# CPU_Board.net
KiCad netlist of a schematic drawn in EAGLE
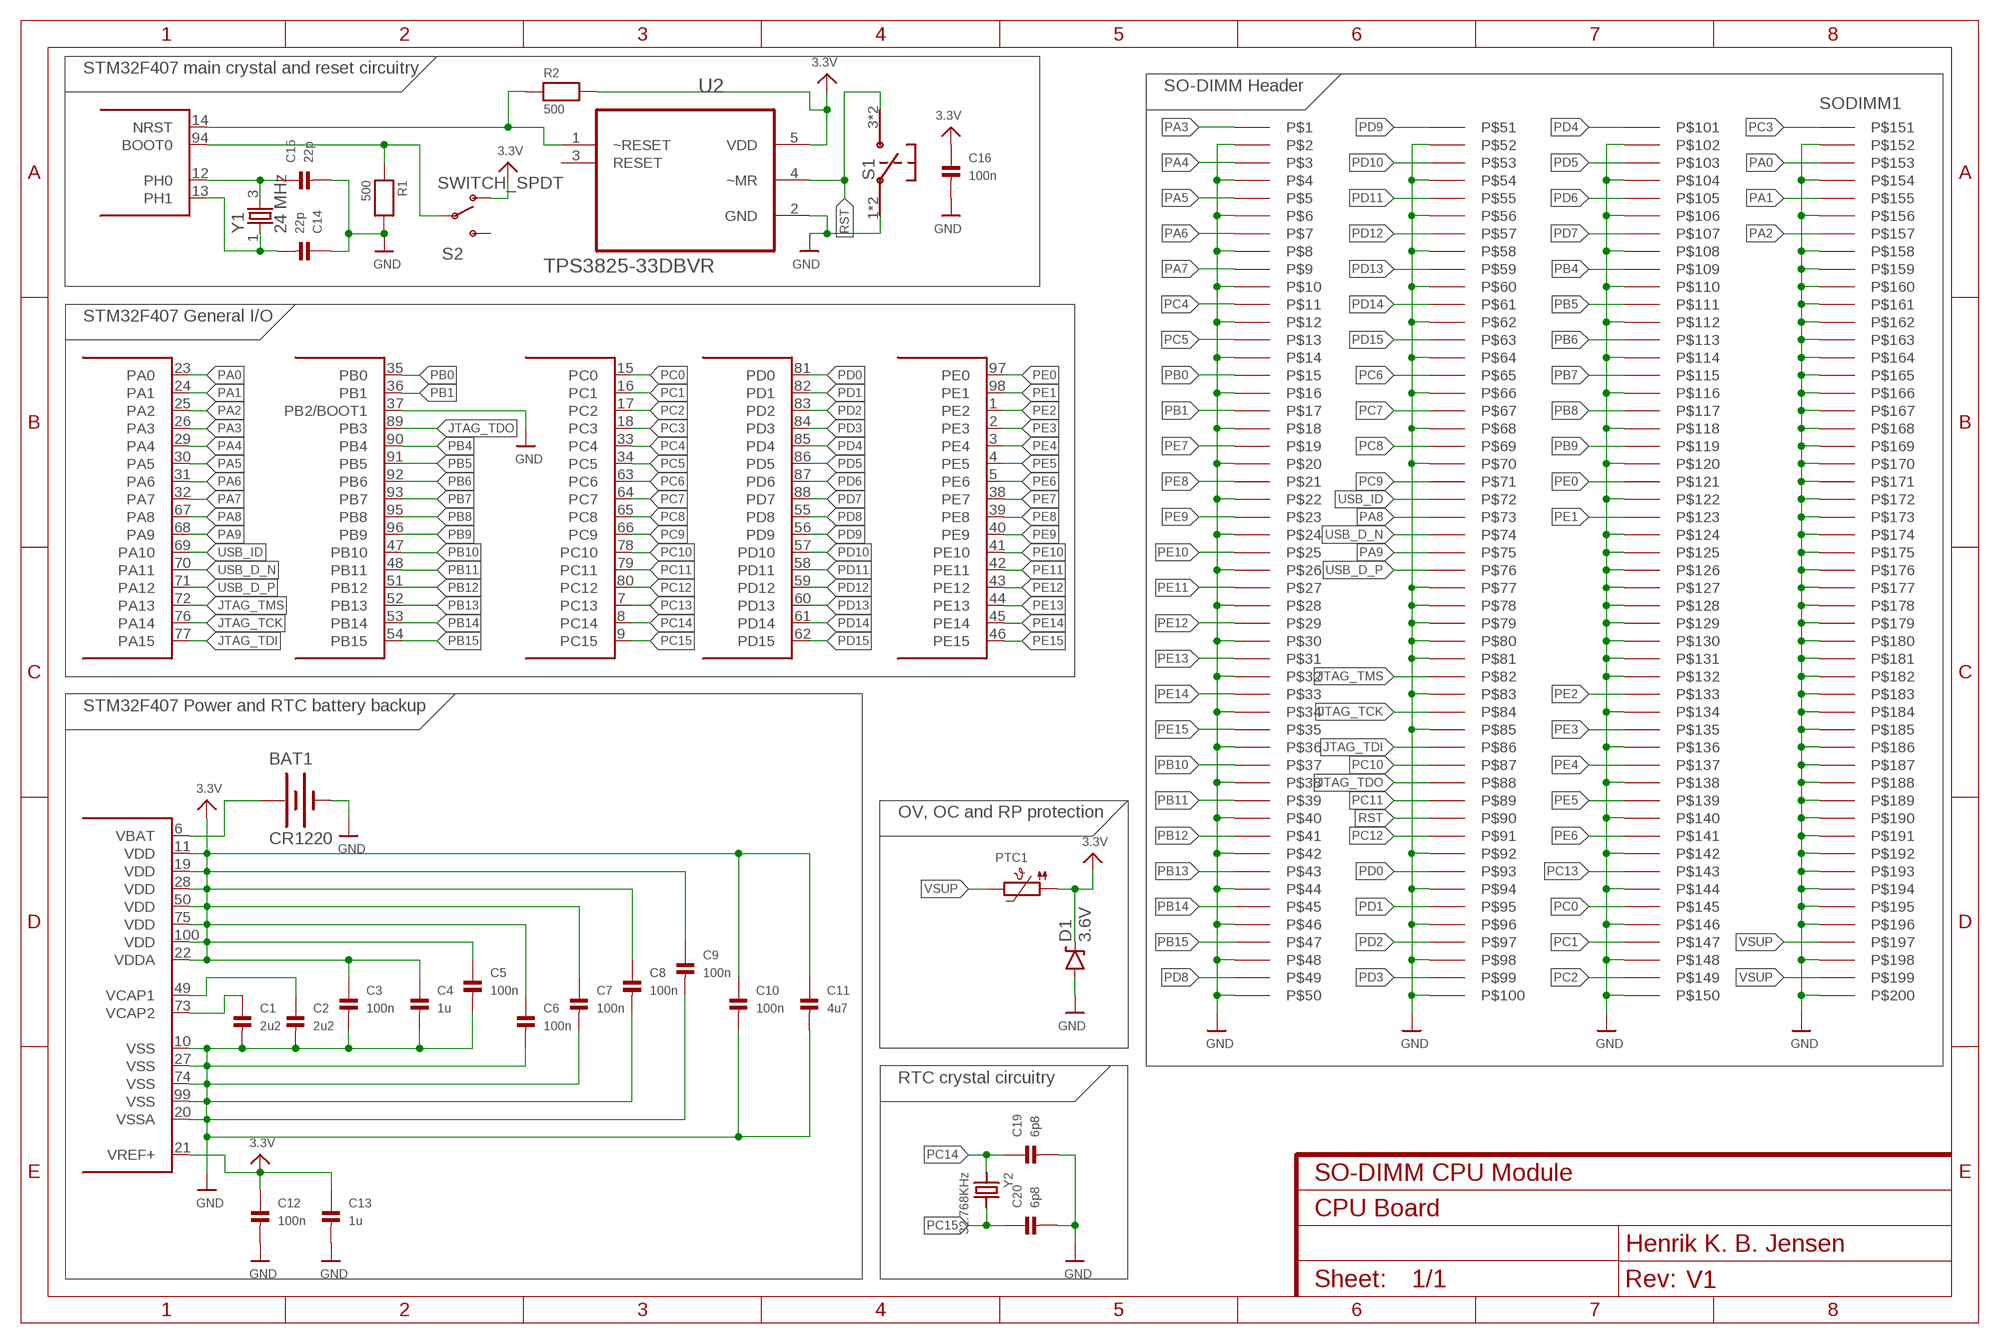
[diagram p0: schematic, sheet 1]

(export (version "E")
  (design (tool "Eeschema 10.0.6"))
  (components
    (comp (ref "BAT1")
      (value "CR1220")
      (footprint "eagle-import:BATTCON_12MM_PTH")
      (libsource (lib "eagle-import") (part "BATTERY12PTH"))
    )
    (comp (ref "C1")
      (value "2u2")
      (footprint "eagle-import:_0603")
      (libsource (lib "eagle-import") (part "CAP_CERAMIC_0603"))
    )
    (comp (ref "C2")
      (value "2u2")
      (footprint "eagle-import:_0603")
      (libsource (lib "eagle-import") (part "CAP_CERAMIC_0603"))
    )
    (comp (ref "C3")
      (value "100n")
      (footprint "eagle-import:_0603")
      (libsource (lib "eagle-import") (part "CAP_CERAMIC_0603"))
    )
    (comp (ref "C4")
      (value "1u")
      (footprint "eagle-import:_0603")
      (libsource (lib "eagle-import") (part "CAP_CERAMIC_0603"))
    )
    (comp (ref "C5")
      (value "100n")
      (footprint "eagle-import:_0603")
      (libsource (lib "eagle-import") (part "CAP_CERAMIC_0603"))
    )
    (comp (ref "C6")
      (value "100n")
      (footprint "eagle-import:_0603")
      (libsource (lib "eagle-import") (part "CAP_CERAMIC_0603"))
    )
    (comp (ref "C7")
      (value "100n")
      (footprint "eagle-import:_0603")
      (libsource (lib "eagle-import") (part "CAP_CERAMIC_0603"))
    )
    (comp (ref "C8")
      (value "100n")
      (footprint "eagle-import:_0603")
      (libsource (lib "eagle-import") (part "CAP_CERAMIC_0603"))
    )
    (comp (ref "C9")
      (value "100n")
      (footprint "eagle-import:_0603")
      (libsource (lib "eagle-import") (part "CAP_CERAMIC_0603"))
    )
    (comp (ref "C10")
      (value "100n")
      (footprint "eagle-import:_0603")
      (libsource (lib "eagle-import") (part "CAP_CERAMIC_0603"))
    )
    (comp (ref "C11")
      (value "4u7")
      (footprint "eagle-import:_0603")
      (libsource (lib "eagle-import") (part "CAP_CERAMIC_0603"))
    )
    (comp (ref "C12")
      (value "100n")
      (footprint "eagle-import:_0603")
      (libsource (lib "eagle-import") (part "CAP_CERAMIC_0603"))
    )
    (comp (ref "C13")
      (value "1u")
      (footprint "eagle-import:_0603")
      (libsource (lib "eagle-import") (part "CAP_CERAMIC_0603"))
    )
    (comp (ref "C14")
      (value "22p")
      (footprint "eagle-import:_0603")
      (libsource (lib "eagle-import") (part "CAP_CERAMIC_0603"))
    )
    (comp (ref "C15")
      (value "22p")
      (footprint "eagle-import:_0603")
      (libsource (lib "eagle-import") (part "CAP_CERAMIC_0603"))
    )
    (comp (ref "C16")
      (value "100n")
      (footprint "eagle-import:_0603")
      (libsource (lib "eagle-import") (part "CAP_CERAMIC_0603"))
    )
    (comp (ref "C19")
      (value "6p8")
      (footprint "eagle-import:_0603")
      (libsource (lib "eagle-import") (part "CAP_CERAMIC_0603"))
    )
    (comp (ref "C20")
      (value "6p8")
      (footprint "eagle-import:_0603")
      (libsource (lib "eagle-import") (part "CAP_CERAMIC_0603"))
    )
    (comp (ref "D1")
      (value "3.6V")
      (footprint "eagle-import:SOD-323")
      (libsource (lib "eagle-import") (part "DIODE-ZENER3.3V"))
    )
    (comp (ref "PTC1")
      (value "PTC1206")
      (footprint "eagle-import:1206")
      (libsource (lib "eagle-import") (part "PTC1206"))
    )
    (comp (ref "R1")
      (value "500")
      (footprint "eagle-import:_0603")
      (libsource (lib "eagle-import") (part "RESISTOR_0603"))
    )
    (comp (ref "R2")
      (value "500")
      (footprint "eagle-import:_0603")
      (libsource (lib "eagle-import") (part "RESISTOR_0603"))
    )
    (comp (ref "S1")
      (value "PTS645SM43SMTR92")
      (footprint "eagle-import:PTS645")
      (libsource (lib "eagle-import") (part "PTS645SM43SMTR92"))
    )
    (comp (ref "S2")
      (value "SWITCH_SPDT")
      (footprint "eagle-import:KPS-1290")
      (libsource (lib "eagle-import") (part "SWITCH_SPDT"))
    )
    (comp (ref "SODIMM1")
      (value "SODIMM_BOARDSMALL")
      (footprint "eagle-import:SODIMM_BOARD_SMALLER-67.6X35")
      (libsource (lib "eagle-import") (part "SODIMM_BOARDSMALL"))
    )
    (comp (ref "U1")
      (value "STM32F4-100")
      (footprint "eagle-import:SQFP-S-14X14-100")
      (libsource (lib "eagle-import") (part "STM32F4-100"))
    )
    (comp (ref "U2")
      (value "TPS3825-33DBVR")
      (footprint "eagle-import:SOT95P280X145-5N")
      (libsource (lib "eagle-import") (part "TPS3825-33DBVR"))
    )
    (comp (ref "Y1")
      (value "24 MHz")
      (footprint "eagle-import:CRYSTAL-4PIN")
      (libsource (lib "eagle-import") (part "CRYSTAL4PIN"))
    )
    (comp (ref "Y2")
      (value "32.768KHz")
      (footprint "eagle-import:CRYSTAL_CYL_2X6MM_SMT")
      (libsource (lib "eagle-import") (part "CRYSTAL32.768"))
    )
  )
  (nets
    (net (code "1") (name "3.3V") (class "Default")
      (node (ref "C10") (pin "1") (pinfunction "P$1_1") (pintype "passive"))
      (node (ref "C11") (pin "1") (pinfunction "P$1_1") (pintype "passive"))
      (node (ref "C12") (pin "1") (pinfunction "P$1_1") (pintype "passive"))
      (node (ref "C13") (pin "1") (pinfunction "P$1_1") (pintype "passive"))
      (node (ref "C16") (pin "1") (pinfunction "P$1_1") (pintype "passive"))
      (node (ref "C3") (pin "1") (pinfunction "P$1_1") (pintype "passive"))
      (node (ref "C4") (pin "1") (pinfunction "P$1_1") (pintype "passive"))
      (node (ref "C5") (pin "1") (pinfunction "P$1_1") (pintype "passive"))
      (node (ref "C6") (pin "1") (pinfunction "P$1_1") (pintype "passive"))
      (node (ref "C7") (pin "1") (pinfunction "P$1_1") (pintype "passive"))
      (node (ref "C8") (pin "1") (pinfunction "P$1_1") (pintype "passive"))
      (node (ref "C9") (pin "1") (pinfunction "P$1_1") (pintype "passive"))
      (node (ref "D1") (pin "C") (pinfunction "C_C") (pintype "passive"))
      (node (ref "PTC1") (pin "1") (pinfunction "1_1") (pintype "passive"))
      (node (ref "R2") (pin "2") (pinfunction "2_2") (pintype "passive"))
      (node (ref "S2") (pin "O") (pinfunction "O_O") (pintype "passive"))
      (node (ref "U1") (pin "100") (pinfunction "VDD_100") (pintype "power_in"))
      (node (ref "U1") (pin "11") (pinfunction "VDD_11") (pintype "power_in"))
      (node (ref "U1") (pin "19") (pinfunction "VDD_19") (pintype "power_in"))
      (node (ref "U1") (pin "21") (pinfunction "VREF+_21") (pintype "passive"))
      (node (ref "U1") (pin "22") (pinfunction "VDDA_22") (pintype "power_in"))
      (node (ref "U1") (pin "28") (pinfunction "VDD_28") (pintype "power_in"))
      (node (ref "U1") (pin "50") (pinfunction "VDD_50") (pintype "power_in"))
      (node (ref "U1") (pin "75") (pinfunction "VDD_75") (pintype "power_in"))
      (node (ref "U2") (pin "5") (pinfunction "VDD_5") (pintype "power_in"))
    )
    (net (code "2") (name "GND") (class "Default")
      (node (ref "BAT1") (pin "GND") (pinfunction "-_GND") (pintype "power_in"))
      (node (ref "C1") (pin "2") (pinfunction "P$2_2") (pintype "passive"))
      (node (ref "C10") (pin "2") (pinfunction "P$2_2") (pintype "passive"))
      (node (ref "C11") (pin "2") (pinfunction "P$2_2") (pintype "passive"))
      (node (ref "C12") (pin "2") (pinfunction "P$2_2") (pintype "passive"))
      (node (ref "C13") (pin "2") (pinfunction "P$2_2") (pintype "passive"))
      (node (ref "C14") (pin "1") (pinfunction "P$1_1") (pintype "passive"))
      (node (ref "C15") (pin "2") (pinfunction "P$2_2") (pintype "passive"))
      (node (ref "C16") (pin "2") (pinfunction "P$2_2") (pintype "passive"))
      (node (ref "C19") (pin "2") (pinfunction "P$2_2") (pintype "passive"))
      (node (ref "C2") (pin "2") (pinfunction "P$2_2") (pintype "passive"))
      (node (ref "C20") (pin "2") (pinfunction "P$2_2") (pintype "passive"))
      (node (ref "C3") (pin "2") (pinfunction "P$2_2") (pintype "passive"))
      (node (ref "C4") (pin "2") (pinfunction "P$2_2") (pintype "passive"))
      (node (ref "C5") (pin "2") (pinfunction "P$2_2") (pintype "passive"))
      (node (ref "C6") (pin "2") (pinfunction "P$2_2") (pintype "passive"))
      (node (ref "C7") (pin "2") (pinfunction "P$2_2") (pintype "passive"))
      (node (ref "C8") (pin "2") (pinfunction "P$2_2") (pintype "passive"))
      (node (ref "C9") (pin "2") (pinfunction "P$2_2") (pintype "passive"))
      (node (ref "D1") (pin "A") (pinfunction "A_A") (pintype "passive"))
      (node (ref "R1") (pin "2") (pinfunction "2_2") (pintype "passive"))
      (node (ref "S1") (pin "1") (pinfunction "P$1_1") (pintype "passive"))
      (node (ref "S1") (pin "2") (pinfunction "P$1_2") (pintype "passive"))
      (node (ref "SODIMM1") (pin "10") (pinfunction "P$10_10") (pintype "bidirectional"))
      (node (ref "SODIMM1") (pin "100") (pinfunction "P$100_100") (pintype "bidirectional"))
      (node (ref "SODIMM1") (pin "102") (pinfunction "P$102_102") (pintype "bidirectional"))
      (node (ref "SODIMM1") (pin "104") (pinfunction "P$104_104") (pintype "bidirectional"))
      (node (ref "SODIMM1") (pin "106") (pinfunction "P$106_106") (pintype "bidirectional"))
      (node (ref "SODIMM1") (pin "108") (pinfunction "P$108_108") (pintype "bidirectional"))
      (node (ref "SODIMM1") (pin "110") (pinfunction "P$110_110") (pintype "bidirectional"))
      (node (ref "SODIMM1") (pin "112") (pinfunction "P$112_112") (pintype "bidirectional"))
      (node (ref "SODIMM1") (pin "114") (pinfunction "P$114_114") (pintype "bidirectional"))
      (node (ref "SODIMM1") (pin "116") (pinfunction "P$116_116") (pintype "bidirectional"))
      (node (ref "SODIMM1") (pin "118") (pinfunction "P$118_118") (pintype "bidirectional"))
      (node (ref "SODIMM1") (pin "12") (pinfunction "P$12_12") (pintype "bidirectional"))
      (node (ref "SODIMM1") (pin "120") (pinfunction "P$120_120") (pintype "bidirectional"))
      (node (ref "SODIMM1") (pin "122") (pinfunction "P$122_122") (pintype "bidirectional"))
      (node (ref "SODIMM1") (pin "124") (pinfunction "P$124_124") (pintype "bidirectional"))
      (node (ref "SODIMM1") (pin "125") (pinfunction "P$125_125") (pintype "bidirectional"))
      (node (ref "SODIMM1") (pin "126") (pinfunction "P$126_126") (pintype "bidirectional"))
      (node (ref "SODIMM1") (pin "127") (pinfunction "P$127_127") (pintype "bidirectional"))
      (node (ref "SODIMM1") (pin "128") (pinfunction "P$128_128") (pintype "bidirectional"))
      (node (ref "SODIMM1") (pin "129") (pinfunction "P$129_129") (pintype "bidirectional"))
      (node (ref "SODIMM1") (pin "130") (pinfunction "P$130_130") (pintype "bidirectional"))
      (node (ref "SODIMM1") (pin "131") (pinfunction "P$131_131") (pintype "bidirectional"))
      (node (ref "SODIMM1") (pin "132") (pinfunction "P$132_132") (pintype "bidirectional"))
      (node (ref "SODIMM1") (pin "134") (pinfunction "P$134_134") (pintype "bidirectional"))
      (node (ref "SODIMM1") (pin "136") (pinfunction "P$136_136") (pintype "bidirectional"))
      (node (ref "SODIMM1") (pin "138") (pinfunction "P$138_138") (pintype "bidirectional"))
      (node (ref "SODIMM1") (pin "14") (pinfunction "P$14_14") (pintype "bidirectional"))
      (node (ref "SODIMM1") (pin "140") (pinfunction "P$140_140") (pintype "bidirectional"))
      (node (ref "SODIMM1") (pin "142") (pinfunction "P$142_142") (pintype "bidirectional"))
      (node (ref "SODIMM1") (pin "144") (pinfunction "P$144_144") (pintype "bidirectional"))
      (node (ref "SODIMM1") (pin "146") (pinfunction "P$146_146") (pintype "bidirectional"))
      (node (ref "SODIMM1") (pin "148") (pinfunction "P$148_148") (pintype "bidirectional"))
      (node (ref "SODIMM1") (pin "150") (pinfunction "P$150_150") (pintype "bidirectional"))
      (node (ref "SODIMM1") (pin "152") (pinfunction "P$152_152") (pintype "bidirectional"))
      (node (ref "SODIMM1") (pin "154") (pinfunction "P$154_154") (pintype "bidirectional"))
      (node (ref "SODIMM1") (pin "156") (pinfunction "P$156_156") (pintype "bidirectional"))
      (node (ref "SODIMM1") (pin "158") (pinfunction "P$158_158") (pintype "bidirectional"))
      (node (ref "SODIMM1") (pin "159") (pinfunction "P$159_159") (pintype "bidirectional"))
      (node (ref "SODIMM1") (pin "16") (pinfunction "P$16_16") (pintype "bidirectional"))
      (node (ref "SODIMM1") (pin "160") (pinfunction "P$160_160") (pintype "bidirectional"))
      (node (ref "SODIMM1") (pin "161") (pinfunction "P$161_161") (pintype "bidirectional"))
      (node (ref "SODIMM1") (pin "162") (pinfunction "P$162_162") (pintype "bidirectional"))
      (node (ref "SODIMM1") (pin "163") (pinfunction "P$163_163") (pintype "bidirectional"))
      (node (ref "SODIMM1") (pin "164") (pinfunction "P$164_164") (pintype "bidirectional"))
      (node (ref "SODIMM1") (pin "165") (pinfunction "P$165_165") (pintype "bidirectional"))
      (node (ref "SODIMM1") (pin "166") (pinfunction "P$166_166") (pintype "bidirectional"))
      (node (ref "SODIMM1") (pin "167") (pinfunction "P$167_167") (pintype "bidirectional"))
      (node (ref "SODIMM1") (pin "168") (pinfunction "P$168_168") (pintype "bidirectional"))
      (node (ref "SODIMM1") (pin "169") (pinfunction "P$169_169") (pintype "bidirectional"))
      (node (ref "SODIMM1") (pin "170") (pinfunction "P$170_170") (pintype "bidirectional"))
      (node (ref "SODIMM1") (pin "171") (pinfunction "P$171_171") (pintype "bidirectional"))
      (node (ref "SODIMM1") (pin "172") (pinfunction "P$172_172") (pintype "bidirectional"))
      (node (ref "SODIMM1") (pin "173") (pinfunction "P$173_173") (pintype "bidirectional"))
      (node (ref "SODIMM1") (pin "174") (pinfunction "P$174_174") (pintype "bidirectional"))
      (node (ref "SODIMM1") (pin "175") (pinfunction "P$175_175") (pintype "bidirectional"))
      (node (ref "SODIMM1") (pin "176") (pinfunction "P$176_176") (pintype "bidirectional"))
      (node (ref "SODIMM1") (pin "177") (pinfunction "P$177_177") (pintype "bidirectional"))
      (node (ref "SODIMM1") (pin "178") (pinfunction "P$178_178") (pintype "bidirectional"))
      (node (ref "SODIMM1") (pin "179") (pinfunction "P$179_179") (pintype "bidirectional"))
      (node (ref "SODIMM1") (pin "18") (pinfunction "P$18_18") (pintype "bidirectional"))
      (node (ref "SODIMM1") (pin "180") (pinfunction "P$180_180") (pintype "bidirectional"))
      (node (ref "SODIMM1") (pin "181") (pinfunction "P$181_181") (pintype "bidirectional"))
      (node (ref "SODIMM1") (pin "182") (pinfunction "P$182_182") (pintype "bidirectional"))
      (node (ref "SODIMM1") (pin "183") (pinfunction "P$183_183") (pintype "bidirectional"))
      (node (ref "SODIMM1") (pin "184") (pinfunction "P$184_184") (pintype "bidirectional"))
      (node (ref "SODIMM1") (pin "185") (pinfunction "P$185_185") (pintype "bidirectional"))
      (node (ref "SODIMM1") (pin "186") (pinfunction "P$186_186") (pintype "bidirectional"))
      (node (ref "SODIMM1") (pin "187") (pinfunction "P$187_187") (pintype "bidirectional"))
      (node (ref "SODIMM1") (pin "188") (pinfunction "P$188_188") (pintype "bidirectional"))
      (node (ref "SODIMM1") (pin "189") (pinfunction "P$189_189") (pintype "bidirectional"))
      (node (ref "SODIMM1") (pin "190") (pinfunction "P$190_190") (pintype "bidirectional"))
      (node (ref "SODIMM1") (pin "191") (pinfunction "P$191_191") (pintype "bidirectional"))
      (node (ref "SODIMM1") (pin "192") (pinfunction "P$192_192") (pintype "bidirectional"))
      (node (ref "SODIMM1") (pin "193") (pinfunction "P$193_193") (pintype "bidirectional"))
      (node (ref "SODIMM1") (pin "194") (pinfunction "P$194_194") (pintype "bidirectional"))
      (node (ref "SODIMM1") (pin "195") (pinfunction "P$195_195") (pintype "bidirectional"))
      (node (ref "SODIMM1") (pin "196") (pinfunction "P$196_196") (pintype "bidirectional"))
      (node (ref "SODIMM1") (pin "198") (pinfunction "P$198_198") (pintype "bidirectional"))
      (node (ref "SODIMM1") (pin "2") (pinfunction "P$2_2") (pintype "bidirectional"))
      (node (ref "SODIMM1") (pin "20") (pinfunction "P$20_20") (pintype "bidirectional"))
      (node (ref "SODIMM1") (pin "200") (pinfunction "P$200_200") (pintype "bidirectional"))
      (node (ref "SODIMM1") (pin "22") (pinfunction "P$22_22") (pintype "bidirectional"))
      (node (ref "SODIMM1") (pin "24") (pinfunction "P$24_24") (pintype "bidirectional"))
      (node (ref "SODIMM1") (pin "26") (pinfunction "P$26_26") (pintype "bidirectional"))
      (node (ref "SODIMM1") (pin "28") (pinfunction "P$28_28") (pintype "bidirectional"))
      (node (ref "SODIMM1") (pin "30") (pinfunction "P$30_30") (pintype "bidirectional"))
      (node (ref "SODIMM1") (pin "32") (pinfunction "P$32_32") (pintype "bidirectional"))
      (node (ref "SODIMM1") (pin "34") (pinfunction "P$34_34") (pintype "bidirectional"))
      (node (ref "SODIMM1") (pin "36") (pinfunction "P$36_36") (pintype "bidirectional"))
      (node (ref "SODIMM1") (pin "38") (pinfunction "P$38_38") (pintype "bidirectional"))
      (node (ref "SODIMM1") (pin "4") (pinfunction "P$4_4") (pintype "bidirectional"))
      (node (ref "SODIMM1") (pin "40") (pinfunction "P$40_40") (pintype "bidirectional"))
      (node (ref "SODIMM1") (pin "42") (pinfunction "P$42_42") (pintype "bidirectional"))
      (node (ref "SODIMM1") (pin "44") (pinfunction "P$44_44") (pintype "bidirectional"))
      (node (ref "SODIMM1") (pin "46") (pinfunction "P$46_46") (pintype "bidirectional"))
      (node (ref "SODIMM1") (pin "48") (pinfunction "P$48_48") (pintype "bidirectional"))
      (node (ref "SODIMM1") (pin "50") (pinfunction "P$50_50") (pintype "bidirectional"))
      (node (ref "SODIMM1") (pin "52") (pinfunction "P$52_52") (pintype "bidirectional"))
      (node (ref "SODIMM1") (pin "54") (pinfunction "P$54_54") (pintype "bidirectional"))
      (node (ref "SODIMM1") (pin "56") (pinfunction "P$56_56") (pintype "bidirectional"))
      (node (ref "SODIMM1") (pin "58") (pinfunction "P$58_58") (pintype "bidirectional"))
      (node (ref "SODIMM1") (pin "6") (pinfunction "P$6_6") (pintype "bidirectional"))
      (node (ref "SODIMM1") (pin "60") (pinfunction "P$60_60") (pintype "bidirectional"))
      (node (ref "SODIMM1") (pin "62") (pinfunction "P$62_62") (pintype "bidirectional"))
      (node (ref "SODIMM1") (pin "64") (pinfunction "P$64_64") (pintype "bidirectional"))
      (node (ref "SODIMM1") (pin "66") (pinfunction "P$66_66") (pintype "bidirectional"))
      (node (ref "SODIMM1") (pin "68") (pinfunction "P$68_68") (pintype "bidirectional"))
      (node (ref "SODIMM1") (pin "70") (pinfunction "P$70_70") (pintype "bidirectional"))
      (node (ref "SODIMM1") (pin "77") (pinfunction "P$77_77") (pintype "bidirectional"))
      (node (ref "SODIMM1") (pin "78") (pinfunction "P$78_78") (pintype "bidirectional"))
      (node (ref "SODIMM1") (pin "79") (pinfunction "P$79_79") (pintype "bidirectional"))
      (node (ref "SODIMM1") (pin "8") (pinfunction "P$8_8") (pintype "bidirectional"))
      (node (ref "SODIMM1") (pin "80") (pinfunction "P$80_80") (pintype "bidirectional"))
      (node (ref "SODIMM1") (pin "81") (pinfunction "P$81_81") (pintype "bidirectional"))
      (node (ref "SODIMM1") (pin "83") (pinfunction "P$83_83") (pintype "bidirectional"))
      (node (ref "SODIMM1") (pin "85") (pinfunction "P$85_85") (pintype "bidirectional"))
      (node (ref "SODIMM1") (pin "92") (pinfunction "P$92_92") (pintype "bidirectional"))
      (node (ref "SODIMM1") (pin "94") (pinfunction "P$94_94") (pintype "bidirectional"))
      (node (ref "SODIMM1") (pin "96") (pinfunction "P$96_96") (pintype "bidirectional"))
      (node (ref "SODIMM1") (pin "98") (pinfunction "P$98_98") (pintype "bidirectional"))
      (node (ref "U1") (pin "10") (pinfunction "VSS_10") (pintype "power_in"))
      (node (ref "U1") (pin "20") (pinfunction "VSSA_20") (pintype "power_in"))
      (node (ref "U1") (pin "27") (pinfunction "VSS_27") (pintype "power_in"))
      (node (ref "U1") (pin "37") (pinfunction "PB2/BOOT1_37") (pintype "bidirectional"))
      (node (ref "U1") (pin "74") (pinfunction "VSS_74") (pintype "power_in"))
      (node (ref "U1") (pin "99") (pinfunction "VSS_99") (pintype "power_in"))
      (node (ref "U2") (pin "2") (pinfunction "GND_2") (pintype "passive"))
    )
    (net (code "3") (name "JTAG_TCK") (class "Default")
      (node (ref "SODIMM1") (pin "84") (pinfunction "P$84_84") (pintype "bidirectional"))
      (node (ref "U1") (pin "76") (pinfunction "PA14_76") (pintype "bidirectional"))
    )
    (net (code "4") (name "JTAG_TDI") (class "Default")
      (node (ref "SODIMM1") (pin "86") (pinfunction "P$86_86") (pintype "bidirectional"))
      (node (ref "U1") (pin "77") (pinfunction "PA15_77") (pintype "bidirectional"))
    )
    (net (code "5") (name "JTAG_TDO") (class "Default")
      (node (ref "SODIMM1") (pin "88") (pinfunction "P$88_88") (pintype "bidirectional"))
      (node (ref "U1") (pin "89") (pinfunction "PB3_89") (pintype "bidirectional"))
    )
    (net (code "6") (name "JTAG_TMS") (class "Default")
      (node (ref "SODIMM1") (pin "82") (pinfunction "P$82_82") (pintype "bidirectional"))
      (node (ref "U1") (pin "72") (pinfunction "PA13_72") (pintype "bidirectional"))
    )
    (net (code "7") (name "Net-(BAT1-+)") (class "Default")
      (node (ref "BAT1") (pin "VCC@1") (pinfunction "+_VCC@1") (pintype "power_in"))
      (node (ref "U1") (pin "6") (pinfunction "VBAT_6") (pintype "power_in"))
    )
    (net (code "8") (name "Net-(C1-P$1)") (class "Default")
      (node (ref "C1") (pin "1") (pinfunction "P$1_1") (pintype "passive"))
      (node (ref "U1") (pin "73") (pinfunction "VCAP2_73") (pintype "passive"))
    )
    (net (code "9") (name "Net-(C2-P$1)") (class "Default")
      (node (ref "C2") (pin "1") (pinfunction "P$1_1") (pintype "passive"))
      (node (ref "U1") (pin "49") (pinfunction "VCAP1_49") (pintype "passive"))
    )
    (net (code "10") (name "Net-(C14-P$2)") (class "Default")
      (node (ref "C14") (pin "2") (pinfunction "P$2_2") (pintype "passive"))
      (node (ref "U1") (pin "13") (pinfunction "PH1_13") (pintype "bidirectional"))
      (node (ref "Y1") (pin "1") (pinfunction "1_1") (pintype "passive"))
    )
    (net (code "11") (name "Net-(C15-P$1)") (class "Default")
      (node (ref "C15") (pin "1") (pinfunction "P$1_1") (pintype "passive"))
      (node (ref "U1") (pin "12") (pinfunction "PH0_12") (pintype "bidirectional"))
      (node (ref "Y1") (pin "3") (pinfunction "2_3") (pintype "passive"))
    )
    (net (code "12") (name "Net-(U1G-BOOT0)") (class "Default")
      (node (ref "R1") (pin "1") (pinfunction "1_1") (pintype "passive"))
      (node (ref "S2") (pin "P") (pinfunction "P_P") (pintype "passive"))
      (node (ref "U1") (pin "94") (pinfunction "BOOT0_94") (pintype "bidirectional"))
    )
    (net (code "13") (name "Net-(U1G-NRST)") (class "Default")
      (node (ref "R2") (pin "1") (pinfunction "1_1") (pintype "passive"))
      (node (ref "U1") (pin "14") (pinfunction "NRST_14") (pintype "bidirectional"))
      (node (ref "U2") (pin "1") (pinfunction "~{RESET}_1") (pintype "output"))
    )
    (net (code "14") (name "PA0") (class "Default")
      (node (ref "SODIMM1") (pin "153") (pinfunction "P$153_153") (pintype "bidirectional"))
      (node (ref "U1") (pin "23") (pinfunction "PA0_23") (pintype "bidirectional"))
    )
    (net (code "15") (name "PA1") (class "Default")
      (node (ref "SODIMM1") (pin "155") (pinfunction "P$155_155") (pintype "bidirectional"))
      (node (ref "U1") (pin "24") (pinfunction "PA1_24") (pintype "bidirectional"))
    )
    (net (code "16") (name "PA2") (class "Default")
      (node (ref "SODIMM1") (pin "157") (pinfunction "P$157_157") (pintype "bidirectional"))
      (node (ref "U1") (pin "25") (pinfunction "PA2_25") (pintype "bidirectional"))
    )
    (net (code "17") (name "PA3") (class "Default")
      (node (ref "SODIMM1") (pin "1") (pinfunction "P$1_1") (pintype "bidirectional"))
      (node (ref "U1") (pin "26") (pinfunction "PA3_26") (pintype "bidirectional"))
    )
    (net (code "18") (name "PA4") (class "Default")
      (node (ref "SODIMM1") (pin "3") (pinfunction "P$3_3") (pintype "bidirectional"))
      (node (ref "U1") (pin "29") (pinfunction "PA4_29") (pintype "bidirectional"))
    )
    (net (code "19") (name "PA5") (class "Default")
      (node (ref "SODIMM1") (pin "5") (pinfunction "P$5_5") (pintype "bidirectional"))
      (node (ref "U1") (pin "30") (pinfunction "PA5_30") (pintype "bidirectional"))
    )
    (net (code "20") (name "PA6") (class "Default")
      (node (ref "SODIMM1") (pin "7") (pinfunction "P$7_7") (pintype "bidirectional"))
      (node (ref "U1") (pin "31") (pinfunction "PA6_31") (pintype "bidirectional"))
    )
    (net (code "21") (name "PA7") (class "Default")
      (node (ref "SODIMM1") (pin "9") (pinfunction "P$9_9") (pintype "bidirectional"))
      (node (ref "U1") (pin "32") (pinfunction "PA7_32") (pintype "bidirectional"))
    )
    (net (code "22") (name "PA8") (class "Default")
      (node (ref "SODIMM1") (pin "73") (pinfunction "P$73_73") (pintype "bidirectional"))
      (node (ref "U1") (pin "67") (pinfunction "PA8_67") (pintype "bidirectional"))
    )
    (net (code "23") (name "PA9") (class "Default")
      (node (ref "SODIMM1") (pin "75") (pinfunction "P$75_75") (pintype "bidirectional"))
      (node (ref "U1") (pin "68") (pinfunction "PA9_68") (pintype "bidirectional"))
    )
    (net (code "24") (name "PB0") (class "Default")
      (node (ref "SODIMM1") (pin "15") (pinfunction "P$15_15") (pintype "bidirectional"))
      (node (ref "U1") (pin "35") (pinfunction "PB0_35") (pintype "bidirectional"))
    )
    (net (code "25") (name "PB1") (class "Default")
      (node (ref "SODIMM1") (pin "17") (pinfunction "P$17_17") (pintype "bidirectional"))
      (node (ref "U1") (pin "36") (pinfunction "PB1_36") (pintype "bidirectional"))
    )
    (net (code "26") (name "PB4") (class "Default")
      (node (ref "SODIMM1") (pin "109") (pinfunction "P$109_109") (pintype "bidirectional"))
      (node (ref "U1") (pin "90") (pinfunction "PB4_90") (pintype "bidirectional"))
    )
    (net (code "27") (name "PB5") (class "Default")
      (node (ref "SODIMM1") (pin "111") (pinfunction "P$111_111") (pintype "bidirectional"))
      (node (ref "U1") (pin "91") (pinfunction "PB5_91") (pintype "bidirectional"))
    )
    (net (code "28") (name "PB6") (class "Default")
      (node (ref "SODIMM1") (pin "113") (pinfunction "P$113_113") (pintype "bidirectional"))
      (node (ref "U1") (pin "92") (pinfunction "PB6_92") (pintype "bidirectional"))
    )
    (net (code "29") (name "PB7") (class "Default")
      (node (ref "SODIMM1") (pin "115") (pinfunction "P$115_115") (pintype "bidirectional"))
      (node (ref "U1") (pin "93") (pinfunction "PB7_93") (pintype "bidirectional"))
    )
    (net (code "30") (name "PB8") (class "Default")
      (node (ref "SODIMM1") (pin "117") (pinfunction "P$117_117") (pintype "bidirectional"))
      (node (ref "U1") (pin "95") (pinfunction "PB8_95") (pintype "bidirectional"))
    )
    (net (code "31") (name "PB9") (class "Default")
      (node (ref "SODIMM1") (pin "119") (pinfunction "P$119_119") (pintype "bidirectional"))
      (node (ref "U1") (pin "96") (pinfunction "PB9_96") (pintype "bidirectional"))
    )
    (net (code "32") (name "PB10") (class "Default")
      (node (ref "SODIMM1") (pin "37") (pinfunction "P$37_37") (pintype "bidirectional"))
      (node (ref "U1") (pin "47") (pinfunction "PB10_47") (pintype "bidirectional"))
    )
    (net (code "33") (name "PB11") (class "Default")
      (node (ref "SODIMM1") (pin "39") (pinfunction "P$39_39") (pintype "bidirectional"))
      (node (ref "U1") (pin "48") (pinfunction "PB11_48") (pintype "bidirectional"))
    )
    (net (code "34") (name "PB12") (class "Default")
      (node (ref "SODIMM1") (pin "41") (pinfunction "P$41_41") (pintype "bidirectional"))
      (node (ref "U1") (pin "51") (pinfunction "PB12_51") (pintype "bidirectional"))
    )
    (net (code "35") (name "PB13") (class "Default")
      (node (ref "SODIMM1") (pin "43") (pinfunction "P$43_43") (pintype "bidirectional"))
      (node (ref "U1") (pin "52") (pinfunction "PB13_52") (pintype "bidirectional"))
    )
    (net (code "36") (name "PB14") (class "Default")
      (node (ref "SODIMM1") (pin "45") (pinfunction "P$45_45") (pintype "bidirectional"))
      (node (ref "U1") (pin "53") (pinfunction "PB14_53") (pintype "bidirectional"))
    )
    (net (code "37") (name "PB15") (class "Default")
      (node (ref "SODIMM1") (pin "47") (pinfunction "P$47_47") (pintype "bidirectional"))
      (node (ref "U1") (pin "54") (pinfunction "PB15_54") (pintype "bidirectional"))
    )
    (net (code "38") (name "PC0") (class "Default")
      (node (ref "SODIMM1") (pin "145") (pinfunction "P$145_145") (pintype "bidirectional"))
      (node (ref "U1") (pin "15") (pinfunction "PC0_15") (pintype "bidirectional"))
    )
    (net (code "39") (name "PC1") (class "Default")
      (node (ref "SODIMM1") (pin "147") (pinfunction "P$147_147") (pintype "bidirectional"))
      (node (ref "U1") (pin "16") (pinfunction "PC1_16") (pintype "bidirectional"))
    )
    (net (code "40") (name "PC2") (class "Default")
      (node (ref "SODIMM1") (pin "149") (pinfunction "P$149_149") (pintype "bidirectional"))
      (node (ref "U1") (pin "17") (pinfunction "PC2_17") (pintype "bidirectional"))
    )
    (net (code "41") (name "PC3") (class "Default")
      (node (ref "SODIMM1") (pin "151") (pinfunction "P$151_151") (pintype "bidirectional"))
      (node (ref "U1") (pin "18") (pinfunction "PC3_18") (pintype "bidirectional"))
    )
    (net (code "42") (name "PC4") (class "Default")
      (node (ref "SODIMM1") (pin "11") (pinfunction "P$11_11") (pintype "bidirectional"))
      (node (ref "U1") (pin "33") (pinfunction "PC4_33") (pintype "bidirectional"))
    )
    (net (code "43") (name "PC5") (class "Default")
      (node (ref "SODIMM1") (pin "13") (pinfunction "P$13_13") (pintype "bidirectional"))
      (node (ref "U1") (pin "34") (pinfunction "PC5_34") (pintype "bidirectional"))
    )
    (net (code "44") (name "PC6") (class "Default")
      (node (ref "SODIMM1") (pin "65") (pinfunction "P$65_65") (pintype "bidirectional"))
      (node (ref "U1") (pin "63") (pinfunction "PC6_63") (pintype "bidirectional"))
    )
    (net (code "45") (name "PC7") (class "Default")
      (node (ref "SODIMM1") (pin "67") (pinfunction "P$67_67") (pintype "bidirectional"))
      (node (ref "U1") (pin "64") (pinfunction "PC7_64") (pintype "bidirectional"))
    )
    (net (code "46") (name "PC8") (class "Default")
      (node (ref "SODIMM1") (pin "69") (pinfunction "P$69_69") (pintype "bidirectional"))
      (node (ref "U1") (pin "65") (pinfunction "PC8_65") (pintype "bidirectional"))
    )
    (net (code "47") (name "PC9") (class "Default")
      (node (ref "SODIMM1") (pin "71") (pinfunction "P$71_71") (pintype "bidirectional"))
      (node (ref "U1") (pin "66") (pinfunction "PC9_66") (pintype "bidirectional"))
    )
    (net (code "48") (name "PC10") (class "Default")
      (node (ref "SODIMM1") (pin "87") (pinfunction "P$87_87") (pintype "bidirectional"))
      (node (ref "U1") (pin "78") (pinfunction "PC10_78") (pintype "bidirectional"))
    )
    (net (code "49") (name "PC11") (class "Default")
      (node (ref "SODIMM1") (pin "89") (pinfunction "P$89_89") (pintype "bidirectional"))
      (node (ref "U1") (pin "79") (pinfunction "PC11_79") (pintype "bidirectional"))
    )
    (net (code "50") (name "PC12") (class "Default")
      (node (ref "SODIMM1") (pin "91") (pinfunction "P$91_91") (pintype "bidirectional"))
      (node (ref "U1") (pin "80") (pinfunction "PC12_80") (pintype "bidirectional"))
    )
    (net (code "51") (name "PC13") (class "Default")
      (node (ref "SODIMM1") (pin "143") (pinfunction "P$143_143") (pintype "bidirectional"))
      (node (ref "U1") (pin "7") (pinfunction "PC13_7") (pintype "bidirectional"))
    )
    (net (code "52") (name "PC14") (class "Default")
      (node (ref "C19") (pin "1") (pinfunction "P$1_1") (pintype "passive"))
      (node (ref "U1") (pin "8") (pinfunction "PC14_8") (pintype "bidirectional"))
      (node (ref "Y2") (pin "1") (pinfunction "1_1") (pintype "passive"))
    )
    (net (code "53") (name "PC15") (class "Default")
      (node (ref "C20") (pin "1") (pinfunction "P$1_1") (pintype "passive"))
      (node (ref "U1") (pin "9") (pinfunction "PC15_9") (pintype "bidirectional"))
      (node (ref "Y2") (pin "2") (pinfunction "2_2") (pintype "passive"))
    )
    (net (code "54") (name "PD0") (class "Default")
      (node (ref "SODIMM1") (pin "93") (pinfunction "P$93_93") (pintype "bidirectional"))
      (node (ref "U1") (pin "81") (pinfunction "PD0_81") (pintype "bidirectional"))
    )
    (net (code "55") (name "PD1") (class "Default")
      (node (ref "SODIMM1") (pin "95") (pinfunction "P$95_95") (pintype "bidirectional"))
      (node (ref "U1") (pin "82") (pinfunction "PD1_82") (pintype "bidirectional"))
    )
    (net (code "56") (name "PD2") (class "Default")
      (node (ref "SODIMM1") (pin "97") (pinfunction "P$97_97") (pintype "bidirectional"))
      (node (ref "U1") (pin "83") (pinfunction "PD2_83") (pintype "bidirectional"))
    )
    (net (code "57") (name "PD3") (class "Default")
      (node (ref "SODIMM1") (pin "99") (pinfunction "P$99_99") (pintype "bidirectional"))
      (node (ref "U1") (pin "84") (pinfunction "PD3_84") (pintype "bidirectional"))
    )
    (net (code "58") (name "PD4") (class "Default")
      (node (ref "SODIMM1") (pin "101") (pinfunction "P$101_101") (pintype "bidirectional"))
      (node (ref "U1") (pin "85") (pinfunction "PD4_85") (pintype "bidirectional"))
    )
    (net (code "59") (name "PD5") (class "Default")
      (node (ref "SODIMM1") (pin "103") (pinfunction "P$103_103") (pintype "bidirectional"))
      (node (ref "U1") (pin "86") (pinfunction "PD5_86") (pintype "bidirectional"))
    )
    (net (code "60") (name "PD6") (class "Default")
      (node (ref "SODIMM1") (pin "105") (pinfunction "P$105_105") (pintype "bidirectional"))
      (node (ref "U1") (pin "87") (pinfunction "PD6_87") (pintype "bidirectional"))
    )
    (net (code "61") (name "PD7") (class "Default")
      (node (ref "SODIMM1") (pin "107") (pinfunction "P$107_107") (pintype "bidirectional"))
      (node (ref "U1") (pin "88") (pinfunction "PD7_88") (pintype "bidirectional"))
    )
    (net (code "62") (name "PD8") (class "Default")
      (node (ref "SODIMM1") (pin "49") (pinfunction "P$49_49") (pintype "bidirectional"))
      (node (ref "U1") (pin "55") (pinfunction "PD8_55") (pintype "bidirectional"))
    )
    (net (code "63") (name "PD9") (class "Default")
      (node (ref "SODIMM1") (pin "51") (pinfunction "P$51_51") (pintype "bidirectional"))
      (node (ref "U1") (pin "56") (pinfunction "PD9_56") (pintype "bidirectional"))
    )
    (net (code "64") (name "PD10") (class "Default")
      (node (ref "SODIMM1") (pin "53") (pinfunction "P$53_53") (pintype "bidirectional"))
      (node (ref "U1") (pin "57") (pinfunction "PD10_57") (pintype "bidirectional"))
    )
    (net (code "65") (name "PD11") (class "Default")
      (node (ref "SODIMM1") (pin "55") (pinfunction "P$55_55") (pintype "bidirectional"))
      (node (ref "U1") (pin "58") (pinfunction "PD11_58") (pintype "bidirectional"))
    )
    (net (code "66") (name "PD12") (class "Default")
      (node (ref "SODIMM1") (pin "57") (pinfunction "P$57_57") (pintype "bidirectional"))
      (node (ref "U1") (pin "59") (pinfunction "PD12_59") (pintype "bidirectional"))
    )
    (net (code "67") (name "PD13") (class "Default")
      (node (ref "SODIMM1") (pin "59") (pinfunction "P$59_59") (pintype "bidirectional"))
      (node (ref "U1") (pin "60") (pinfunction "PD13_60") (pintype "bidirectional"))
    )
    (net (code "68") (name "PD14") (class "Default")
      (node (ref "SODIMM1") (pin "61") (pinfunction "P$61_61") (pintype "bidirectional"))
      (node (ref "U1") (pin "61") (pinfunction "PD14_61") (pintype "bidirectional"))
    )
    (net (code "69") (name "PD15") (class "Default")
      (node (ref "SODIMM1") (pin "63") (pinfunction "P$63_63") (pintype "bidirectional"))
      (node (ref "U1") (pin "62") (pinfunction "PD15_62") (pintype "bidirectional"))
    )
    (net (code "70") (name "PE0") (class "Default")
      (node (ref "SODIMM1") (pin "121") (pinfunction "P$121_121") (pintype "bidirectional"))
      (node (ref "U1") (pin "97") (pinfunction "PE0_97") (pintype "bidirectional"))
    )
    (net (code "71") (name "PE1") (class "Default")
      (node (ref "SODIMM1") (pin "123") (pinfunction "P$123_123") (pintype "bidirectional"))
      (node (ref "U1") (pin "98") (pinfunction "PE1_98") (pintype "bidirectional"))
    )
    (net (code "72") (name "PE2") (class "Default")
      (node (ref "SODIMM1") (pin "133") (pinfunction "P$133_133") (pintype "bidirectional"))
      (node (ref "U1") (pin "1") (pinfunction "PE2_1") (pintype "bidirectional"))
    )
    (net (code "73") (name "PE3") (class "Default")
      (node (ref "SODIMM1") (pin "135") (pinfunction "P$135_135") (pintype "bidirectional"))
      (node (ref "U1") (pin "2") (pinfunction "PE3_2") (pintype "bidirectional"))
    )
    (net (code "74") (name "PE4") (class "Default")
      (node (ref "SODIMM1") (pin "137") (pinfunction "P$137_137") (pintype "bidirectional"))
      (node (ref "U1") (pin "3") (pinfunction "PE4_3") (pintype "bidirectional"))
    )
    (net (code "75") (name "PE5") (class "Default")
      (node (ref "SODIMM1") (pin "139") (pinfunction "P$139_139") (pintype "bidirectional"))
      (node (ref "U1") (pin "4") (pinfunction "PE5_4") (pintype "bidirectional"))
    )
    (net (code "76") (name "PE6") (class "Default")
      (node (ref "SODIMM1") (pin "141") (pinfunction "P$141_141") (pintype "bidirectional"))
      (node (ref "U1") (pin "5") (pinfunction "PE6_5") (pintype "bidirectional"))
    )
    (net (code "77") (name "PE7") (class "Default")
      (node (ref "SODIMM1") (pin "19") (pinfunction "P$19_19") (pintype "bidirectional"))
      (node (ref "U1") (pin "38") (pinfunction "PE7_38") (pintype "bidirectional"))
    )
    (net (code "78") (name "PE8") (class "Default")
      (node (ref "SODIMM1") (pin "21") (pinfunction "P$21_21") (pintype "bidirectional"))
      (node (ref "U1") (pin "39") (pinfunction "PE8_39") (pintype "bidirectional"))
    )
    (net (code "79") (name "PE9") (class "Default")
      (node (ref "SODIMM1") (pin "23") (pinfunction "P$23_23") (pintype "bidirectional"))
      (node (ref "U1") (pin "40") (pinfunction "PE9_40") (pintype "bidirectional"))
    )
    (net (code "80") (name "PE10") (class "Default")
      (node (ref "SODIMM1") (pin "25") (pinfunction "P$25_25") (pintype "bidirectional"))
      (node (ref "U1") (pin "41") (pinfunction "PE10_41") (pintype "bidirectional"))
    )
    (net (code "81") (name "PE11") (class "Default")
      (node (ref "SODIMM1") (pin "27") (pinfunction "P$27_27") (pintype "bidirectional"))
      (node (ref "U1") (pin "42") (pinfunction "PE11_42") (pintype "bidirectional"))
    )
    (net (code "82") (name "PE12") (class "Default")
      (node (ref "SODIMM1") (pin "29") (pinfunction "P$29_29") (pintype "bidirectional"))
      (node (ref "U1") (pin "43") (pinfunction "PE12_43") (pintype "bidirectional"))
    )
    (net (code "83") (name "PE13") (class "Default")
      (node (ref "SODIMM1") (pin "31") (pinfunction "P$31_31") (pintype "bidirectional"))
      (node (ref "U1") (pin "44") (pinfunction "PE13_44") (pintype "bidirectional"))
    )
    (net (code "84") (name "PE14") (class "Default")
      (node (ref "SODIMM1") (pin "33") (pinfunction "P$33_33") (pintype "bidirectional"))
      (node (ref "U1") (pin "45") (pinfunction "PE14_45") (pintype "bidirectional"))
    )
    (net (code "85") (name "PE15") (class "Default")
      (node (ref "SODIMM1") (pin "35") (pinfunction "P$35_35") (pintype "bidirectional"))
      (node (ref "U1") (pin "46") (pinfunction "PE15_46") (pintype "bidirectional"))
    )
    (net (code "86") (name "RST") (class "Default")
      (node (ref "S1") (pin "3") (pinfunction "P$2_3") (pintype "passive"))
      (node (ref "S1") (pin "4") (pinfunction "P$2_4") (pintype "passive"))
      (node (ref "SODIMM1") (pin "90") (pinfunction "P$90_90") (pintype "bidirectional"))
      (node (ref "U2") (pin "4") (pinfunction "~{MR}_4") (pintype "input"))
    )
    (net (code "87") (name "USB_D_N") (class "Default")
      (node (ref "SODIMM1") (pin "74") (pinfunction "P$74_74") (pintype "bidirectional"))
      (node (ref "U1") (pin "70") (pinfunction "PA11_70") (pintype "bidirectional"))
    )
    (net (code "88") (name "USB_D_P") (class "Default")
      (node (ref "SODIMM1") (pin "76") (pinfunction "P$76_76") (pintype "bidirectional"))
      (node (ref "U1") (pin "71") (pinfunction "PA12_71") (pintype "bidirectional"))
    )
    (net (code "89") (name "USB_ID") (class "Default")
      (node (ref "SODIMM1") (pin "72") (pinfunction "P$72_72") (pintype "bidirectional"))
      (node (ref "U1") (pin "69") (pinfunction "PA10_69") (pintype "bidirectional"))
    )
    (net (code "90") (name "VSUP") (class "Default")
      (node (ref "PTC1") (pin "2") (pinfunction "2_2") (pintype "passive"))
      (node (ref "SODIMM1") (pin "197") (pinfunction "P$197_197") (pintype "bidirectional"))
      (node (ref "SODIMM1") (pin "199") (pinfunction "P$199_199") (pintype "bidirectional"))
    )
    (net (code "91") (name "unconnected-(S2-PadS)") (class "Default")
      (node (ref "S2") (pin "S") (pinfunction "S_S") (pintype "passive"))
    )
    (net (code "92") (name "unconnected-(U2-RESET-Pad3)") (class "Default")
      (node (ref "U2") (pin "3") (pinfunction "RESET_3") (pintype "output"))
    )
  )
)
